# Group5Approved.net
KiCad netlist of a schematic drawn in EAGLE
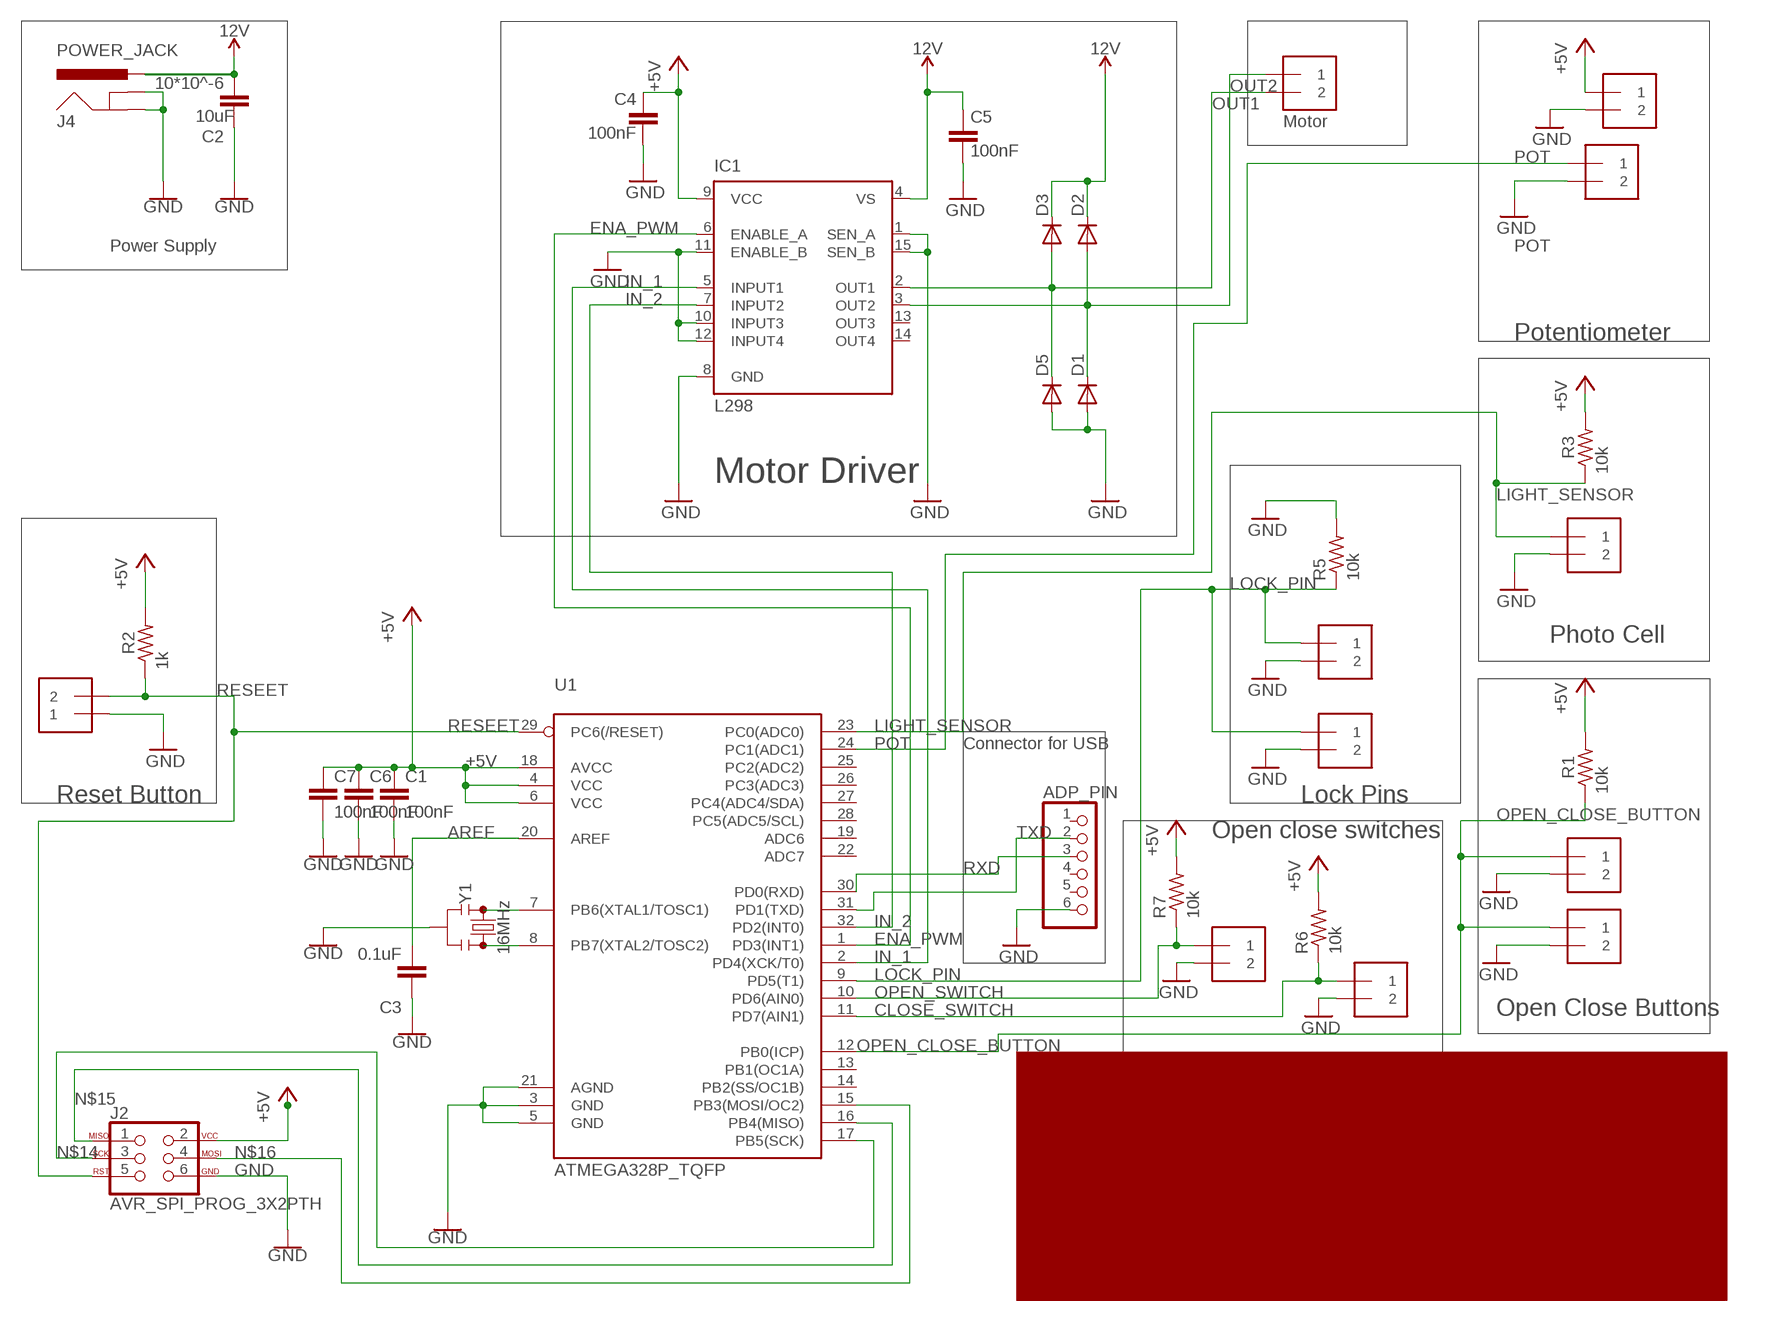
[diagram p0: schematic, sheet 1]

(export (version "E")
  (design (tool "Eeschema 10.0.6"))
  (components
    (comp (ref "ADP_PIN")
      (value "PINHD-1X6")
      (footprint "eagle-import:1X06")
      (libsource (lib "eagle-import") (part "PINHD-1X6"))
    )
    (comp (ref "C1")
      (value "100nF")
      (footprint "eagle-import:C0805")
      (libsource (lib "eagle-import") (part "C-EUC0805"))
    )
    (comp (ref "C2")
      (value "10*10^-6")
      (footprint "eagle-import:C0805")
      (fields (field (name "SPICEPREFIX") "C") (field (name "SPICEPREFIX_1") "10uF"))
      (libsource (lib "eagle-import") (part "C-EUC0805"))
    )
    (comp (ref "C3")
      (value "0.1uF")
      (footprint "eagle-import:C0805")
      (libsource (lib "eagle-import") (part "C-EUC0805"))
    )
    (comp (ref "C4")
      (value "100nF")
      (footprint "eagle-import:C0805")
      (libsource (lib "eagle-import") (part "C-EUC0805"))
    )
    (comp (ref "C5")
      (value "100nF")
      (footprint "eagle-import:C0805")
      (libsource (lib "eagle-import") (part "C-EUC0805"))
    )
    (comp (ref "C6")
      (value "100nF")
      (footprint "eagle-import:C0805")
      (libsource (lib "eagle-import") (part "C-EUC0805"))
    )
    (comp (ref "C7")
      (value "100nF")
      (footprint "eagle-import:C0805")
      (libsource (lib "eagle-import") (part "C-EUC0805"))
    )
    (comp (ref "CLOSESWITCH")
      (value "1X2-3.5MM")
      (footprint "eagle-import:1X2-3.5MM")
      (libsource (lib "eagle-import") (part "1X2-3.5MM"))
    )
    (comp (ref "D1")
      (value "DIODE-DO214AA")
      (footprint "eagle-import:DO214AA")
      (libsource (lib "eagle-import") (part "DIODE-DO214AA"))
    )
    (comp (ref "D2")
      (value "DIODE-DO214AA")
      (footprint "eagle-import:DO214AA")
      (libsource (lib "eagle-import") (part "DIODE-DO214AA"))
    )
    (comp (ref "D3")
      (value "DIODE-DO214AA")
      (footprint "eagle-import:DO214AA")
      (libsource (lib "eagle-import") (part "DIODE-DO214AA"))
    )
    (comp (ref "D5")
      (value "DIODE-DO214AA")
      (footprint "eagle-import:DO214AA")
      (libsource (lib "eagle-import") (part "DIODE-DO214AA"))
    )
    (comp (ref "IC1")
      (value "L298")
      (footprint "eagle-import:MULTIWATT-15")
      (fields (field (name "MPN") "L298N"))
      (libsource (lib "eagle-import") (part "L298"))
    )
    (comp (ref "INSIDE_BUTTON")
      (value "1X2-3.5MM")
      (footprint "eagle-import:1X2-3.5MM")
      (libsource (lib "eagle-import") (part "1X2-3.5MM"))
    )
    (comp (ref "J2")
      (value "AVR_SPI_PROG_3X2PTH")
      (footprint "eagle-import:2X3")
      (libsource (lib "eagle-import") (part "AVR_SPI_PROG_3X2PTH"))
    )
    (comp (ref "J4")
      (value "POWER_JACK")
      (footprint "eagle-import:POWER_JACK_PTH")
      (libsource (lib "eagle-import") (part "POWER_JACK"))
    )
    (comp (ref "LIGHT_SENSOR")
      (value "1X2-3.5MM")
      (footprint "eagle-import:1X2-3.5MM")
      (libsource (lib "eagle-import") (part "1X2-3.5MM"))
    )
    (comp (ref "LOCK_PIN1")
      (value "1X2-3.5MM")
      (footprint "eagle-import:1X2-3.5MM")
      (libsource (lib "eagle-import") (part "1X2-3.5MM"))
    )
    (comp (ref "LOCK_PIN2")
      (value "1X2-3.5MM")
      (footprint "eagle-import:1X2-3.5MM")
      (libsource (lib "eagle-import") (part "1X2-3.5MM"))
    )
    (comp (ref "MOTOR")
      (value "1X2-3.5MM")
      (footprint "eagle-import:1X2-3.5MM")
      (libsource (lib "eagle-import") (part "1X2-3.5MM"))
    )
    (comp (ref "OPEN_SWITCH")
      (value "1X2-3.5MM")
      (footprint "eagle-import:1X2-3.5MM")
      (libsource (lib "eagle-import") (part "1X2-3.5MM"))
    )
    (comp (ref "OUTSIDE_BUTTON")
      (value "1X2-3.5MM")
      (footprint "eagle-import:1X2-3.5MM")
      (libsource (lib "eagle-import") (part "1X2-3.5MM"))
    )
    (comp (ref "POT")
      (value "1X2-3.5MM")
      (footprint "eagle-import:1X2-3.5MM")
      (libsource (lib "eagle-import") (part "1X2-3.5MM"))
    )
    (comp (ref "POTPOWER")
      (value "1X2-3.5MM")
      (footprint "eagle-import:1X2-3.5MM")
      (libsource (lib "eagle-import") (part "1X2-3.5MM"))
    )
    (comp (ref "R1")
      (value "10k")
      (footprint "eagle-import:M0805")
      (libsource (lib "eagle-import") (part "R-US_M0805"))
    )
    (comp (ref "R2")
      (value "1k")
      (footprint "eagle-import:M0805")
      (libsource (lib "eagle-import") (part "R-US_M0805"))
    )
    (comp (ref "R3")
      (value "10k")
      (footprint "eagle-import:M0805")
      (libsource (lib "eagle-import") (part "R-US_M0805"))
    )
    (comp (ref "R5")
      (value "10k")
      (footprint "eagle-import:M0805")
      (libsource (lib "eagle-import") (part "R-US_M0805"))
    )
    (comp (ref "R6")
      (value "10k")
      (footprint "eagle-import:M0805")
      (libsource (lib "eagle-import") (part "R-US_M0805"))
    )
    (comp (ref "R7")
      (value "10k")
      (footprint "eagle-import:M0805")
      (libsource (lib "eagle-import") (part "R-US_M0805"))
    )
    (comp (ref "RESETBUTTON")
      (value "1X2-3.5MM")
      (footprint "eagle-import:1X2-3.5MM")
      (libsource (lib "eagle-import") (part "1X2-3.5MM"))
    )
    (comp (ref "U1")
      (value "ATMEGA328P_TQFP")
      (footprint "eagle-import:TQFP32-08")
      (libsource (lib "eagle-import") (part "ATMEGA328P_TQFP"))
    )
    (comp (ref "Y1")
      (value "16MHz")
      (footprint "eagle-import:RESONATOR-SMD-3.2X1.3")
      (libsource (lib "eagle-import") (part "RESONATOR-16MHZSMD_3.2X1.3"))
    )
  )
  (nets
    (net (code "1") (name "+5V") (class "Default")
      (node (ref "C1") (pin "1") (pinfunction "1_1") (pintype "passive"))
      (node (ref "C4") (pin "1") (pinfunction "1_1") (pintype "passive"))
      (node (ref "C6") (pin "1") (pinfunction "1_1") (pintype "passive"))
      (node (ref "C7") (pin "1") (pinfunction "1_1") (pintype "passive"))
      (node (ref "IC1") (pin "9") (pinfunction "VCC_9") (pintype "power_in"))
      (node (ref "J2") (pin "2") (pinfunction "2_2") (pintype "passive"))
      (node (ref "POTPOWER") (pin "1") (pinfunction "1_1") (pintype "passive"))
      (node (ref "R1") (pin "2") (pinfunction "2_2") (pintype "passive"))
      (node (ref "R2") (pin "2") (pinfunction "2_2") (pintype "passive"))
      (node (ref "R3") (pin "2") (pinfunction "2_2") (pintype "passive"))
      (node (ref "R6") (pin "2") (pinfunction "2_2") (pintype "passive"))
      (node (ref "R7") (pin "2") (pinfunction "2_2") (pintype "passive"))
      (node (ref "U1") (pin "18") (pinfunction "AVCC_18") (pintype "bidirectional"))
      (node (ref "U1") (pin "4") (pinfunction "VCC_4") (pintype "bidirectional"))
      (node (ref "U1") (pin "6") (pinfunction "VCC_6") (pintype "bidirectional"))
    )
    (net (code "2") (name "/AREF") (class "Default")
      (node (ref "C3") (pin "2") (pinfunction "2_2") (pintype "passive"))
      (node (ref "U1") (pin "20") (pinfunction "AREF_20") (pintype "bidirectional"))
    )
    (net (code "3") (name "/CLOSE_SWITCH") (class "Default")
      (node (ref "CLOSESWITCH") (pin "1") (pinfunction "1_1") (pintype "passive"))
      (node (ref "R6") (pin "1") (pinfunction "1_1") (pintype "passive"))
      (node (ref "U1") (pin "11") (pinfunction "PD7(AIN1)_11") (pintype "bidirectional"))
    )
    (net (code "4") (name "/ENA_PWM") (class "Default")
      (node (ref "IC1") (pin "6") (pinfunction "ENABLE_A_6") (pintype "input"))
      (node (ref "U1") (pin "1") (pinfunction "PD3(INT1)_1") (pintype "bidirectional"))
    )
    (net (code "5") (name "/IN_1") (class "Default")
      (node (ref "IC1") (pin "5") (pinfunction "INPUT1_5") (pintype "input"))
      (node (ref "U1") (pin "2") (pinfunction "PD4(XCK/T0)_2") (pintype "bidirectional"))
    )
    (net (code "6") (name "/IN_2") (class "Default")
      (node (ref "IC1") (pin "7") (pinfunction "INPUT2_7") (pintype "input"))
      (node (ref "U1") (pin "32") (pinfunction "PD2(INT0)_32") (pintype "bidirectional"))
    )
    (net (code "7") (name "/LIGHT_SENSOR") (class "Default")
      (node (ref "LIGHT_SENSOR") (pin "1") (pinfunction "1_1") (pintype "passive"))
      (node (ref "R3") (pin "1") (pinfunction "1_1") (pintype "passive"))
      (node (ref "U1") (pin "23") (pinfunction "PC0(ADC0)_23") (pintype "bidirectional"))
    )
    (net (code "8") (name "/LOCK_PIN") (class "Default")
      (node (ref "LOCK_PIN1") (pin "1") (pinfunction "1_1") (pintype "passive"))
      (node (ref "LOCK_PIN2") (pin "1") (pinfunction "1_1") (pintype "passive"))
      (node (ref "R5") (pin "1") (pinfunction "1_1") (pintype "passive"))
      (node (ref "U1") (pin "9") (pinfunction "PD5(T1)_9") (pintype "bidirectional"))
    )
    (net (code "9") (name "/N$14") (class "Default")
      (node (ref "J2") (pin "3") (pinfunction "3_3") (pintype "passive"))
      (node (ref "U1") (pin "17") (pinfunction "PB5(SCK)_17") (pintype "bidirectional"))
    )
    (net (code "10") (name "/N$15") (class "Default")
      (node (ref "J2") (pin "1") (pinfunction "1_1") (pintype "passive"))
      (node (ref "U1") (pin "16") (pinfunction "PB4(MISO)_16") (pintype "bidirectional"))
    )
    (net (code "11") (name "/N$16") (class "Default")
      (node (ref "J2") (pin "4") (pinfunction "4_4") (pintype "passive"))
      (node (ref "U1") (pin "15") (pinfunction "PB3(MOSI/OC2)_15") (pintype "bidirectional"))
    )
    (net (code "12") (name "/OPEN_CLOSE_BUTTON") (class "Default")
      (node (ref "INSIDE_BUTTON") (pin "1") (pinfunction "1_1") (pintype "passive"))
      (node (ref "OUTSIDE_BUTTON") (pin "1") (pinfunction "1_1") (pintype "passive"))
      (node (ref "R1") (pin "1") (pinfunction "1_1") (pintype "passive"))
      (node (ref "U1") (pin "12") (pinfunction "PB0(ICP)_12") (pintype "bidirectional"))
    )
    (net (code "13") (name "/OPEN_SWITCH") (class "Default")
      (node (ref "OPEN_SWITCH") (pin "1") (pinfunction "1_1") (pintype "passive"))
      (node (ref "R7") (pin "1") (pinfunction "1_1") (pintype "passive"))
      (node (ref "U1") (pin "10") (pinfunction "PD6(AIN0)_10") (pintype "bidirectional"))
    )
    (net (code "14") (name "/OUT1") (class "Default")
      (node (ref "D3") (pin "A") (pinfunction "A_A") (pintype "passive"))
      (node (ref "D5") (pin "C") (pinfunction "C_C") (pintype "passive"))
      (node (ref "IC1") (pin "2") (pinfunction "OUT1_2") (pintype "output"))
      (node (ref "MOTOR") (pin "2") (pinfunction "2_2") (pintype "passive"))
    )
    (net (code "15") (name "/OUT2") (class "Default")
      (node (ref "D1") (pin "C") (pinfunction "C_C") (pintype "passive"))
      (node (ref "D2") (pin "A") (pinfunction "A_A") (pintype "passive"))
      (node (ref "IC1") (pin "3") (pinfunction "OUT2_3") (pintype "output"))
      (node (ref "MOTOR") (pin "1") (pinfunction "1_1") (pintype "passive"))
    )
    (net (code "16") (name "/POT") (class "Default")
      (node (ref "POT") (pin "1") (pinfunction "1_1") (pintype "passive"))
      (node (ref "U1") (pin "24") (pinfunction "PC1(ADC1)_24") (pintype "bidirectional"))
    )
    (net (code "17") (name "/RESEET") (class "Default")
      (node (ref "J2") (pin "5") (pinfunction "5_5") (pintype "passive"))
      (node (ref "R2") (pin "1") (pinfunction "1_1") (pintype "passive"))
      (node (ref "RESETBUTTON") (pin "2") (pinfunction "2_2") (pintype "passive"))
      (node (ref "U1") (pin "29") (pinfunction "PC6(/RESET)_29") (pintype "bidirectional"))
    )
    (net (code "18") (name "/RXD") (class "Default")
      (node (ref "ADP_PIN") (pin "3") (pinfunction "3_3") (pintype "passive"))
      (node (ref "U1") (pin "30") (pinfunction "PD0(RXD)_30") (pintype "bidirectional"))
    )
    (net (code "19") (name "/TXD") (class "Default")
      (node (ref "ADP_PIN") (pin "2") (pinfunction "2_2") (pintype "passive"))
      (node (ref "U1") (pin "31") (pinfunction "PD1(TXD)_31") (pintype "bidirectional"))
    )
    (net (code "20") (name "12V") (class "Default")
      (node (ref "C2") (pin "2") (pinfunction "2_2") (pintype "passive"))
      (node (ref "C5") (pin "1") (pinfunction "1_1") (pintype "passive"))
      (node (ref "D2") (pin "C") (pinfunction "C_C") (pintype "passive"))
      (node (ref "D3") (pin "C") (pinfunction "C_C") (pintype "passive"))
      (node (ref "IC1") (pin "4") (pinfunction "VS_4") (pintype "power_in"))
      (node (ref "J4") (pin "PWR") (pinfunction "PWR_PWR") (pintype "bidirectional"))
    )
    (net (code "21") (name "GND") (class "Default")
      (node (ref "ADP_PIN") (pin "6") (pinfunction "6_6") (pintype "passive"))
      (node (ref "C1") (pin "2") (pinfunction "2_2") (pintype "passive"))
      (node (ref "C2") (pin "1") (pinfunction "1_1") (pintype "passive"))
      (node (ref "C3") (pin "1") (pinfunction "1_1") (pintype "passive"))
      (node (ref "C4") (pin "2") (pinfunction "2_2") (pintype "passive"))
      (node (ref "C5") (pin "2") (pinfunction "2_2") (pintype "passive"))
      (node (ref "C6") (pin "2") (pinfunction "2_2") (pintype "passive"))
      (node (ref "C7") (pin "2") (pinfunction "2_2") (pintype "passive"))
      (node (ref "CLOSESWITCH") (pin "2") (pinfunction "2_2") (pintype "passive"))
      (node (ref "D1") (pin "A") (pinfunction "A_A") (pintype "passive"))
      (node (ref "D5") (pin "A") (pinfunction "A_A") (pintype "passive"))
      (node (ref "IC1") (pin "1") (pinfunction "SEN_A_1") (pintype "input"))
      (node (ref "IC1") (pin "10") (pinfunction "INPUT3_10") (pintype "input"))
      (node (ref "IC1") (pin "11") (pinfunction "ENABLE_B_11") (pintype "input"))
      (node (ref "IC1") (pin "12") (pinfunction "INPUT4_12") (pintype "input"))
      (node (ref "IC1") (pin "15") (pinfunction "SEN_B_15") (pintype "input"))
      (node (ref "IC1") (pin "8") (pinfunction "GND_8") (pintype "power_in"))
      (node (ref "INSIDE_BUTTON") (pin "2") (pinfunction "2_2") (pintype "passive"))
      (node (ref "J2") (pin "6") (pinfunction "6_6") (pintype "passive"))
      (node (ref "J4") (pin "GND") (pinfunction "GND_GND") (pintype "bidirectional"))
      (node (ref "J4") (pin "GNDBREAK") (pinfunction "GNDBREAK_GNDBREAK") (pintype "bidirectional"))
      (node (ref "LIGHT_SENSOR") (pin "2") (pinfunction "2_2") (pintype "passive"))
      (node (ref "LOCK_PIN1") (pin "2") (pinfunction "2_2") (pintype "passive"))
      (node (ref "LOCK_PIN2") (pin "2") (pinfunction "2_2") (pintype "passive"))
      (node (ref "OPEN_SWITCH") (pin "2") (pinfunction "2_2") (pintype "passive"))
      (node (ref "OUTSIDE_BUTTON") (pin "2") (pinfunction "2_2") (pintype "passive"))
      (node (ref "POT") (pin "2") (pinfunction "2_2") (pintype "passive"))
      (node (ref "POTPOWER") (pin "2") (pinfunction "2_2") (pintype "passive"))
      (node (ref "R5") (pin "2") (pinfunction "2_2") (pintype "passive"))
      (node (ref "RESETBUTTON") (pin "1") (pinfunction "1_1") (pintype "passive"))
      (node (ref "U1") (pin "21") (pinfunction "AGND_21") (pintype "bidirectional"))
      (node (ref "U1") (pin "3") (pinfunction "GND_3") (pintype "bidirectional"))
      (node (ref "U1") (pin "5") (pinfunction "GND_5") (pintype "bidirectional"))
      (node (ref "Y1") (pin "2") (pinfunction "2_2") (pintype "passive"))
    )
    (net (code "22") (name "Net-(U1-PB6(XTAL1{slash}TOSC1))") (class "Default")
      (node (ref "U1") (pin "7") (pinfunction "PB6(XTAL1/TOSC1)_7") (pintype "bidirectional"))
      (node (ref "Y1") (pin "1") (pinfunction "1_1") (pintype "passive"))
    )
    (net (code "23") (name "Net-(U1-PB7(XTAL2{slash}TOSC2))") (class "Default")
      (node (ref "U1") (pin "8") (pinfunction "PB7(XTAL2/TOSC2)_8") (pintype "bidirectional"))
      (node (ref "Y1") (pin "3") (pinfunction "3_3") (pintype "passive"))
    )
    (net (code "24") (name "unconnected-(ADP_PIN-Pad1)") (class "Default")
      (node (ref "ADP_PIN") (pin "1") (pinfunction "1_1") (pintype "passive"))
    )
    (net (code "25") (name "unconnected-(ADP_PIN-Pad4)") (class "Default")
      (node (ref "ADP_PIN") (pin "4") (pinfunction "4_4") (pintype "passive"))
    )
    (net (code "26") (name "unconnected-(ADP_PIN-Pad5)") (class "Default")
      (node (ref "ADP_PIN") (pin "5") (pinfunction "5_5") (pintype "passive"))
    )
    (net (code "27") (name "unconnected-(IC1-OUT3-Pad13)") (class "Default")
      (node (ref "IC1") (pin "13") (pinfunction "OUT3_13") (pintype "output"))
    )
    (net (code "28") (name "unconnected-(IC1-OUT4-Pad14)") (class "Default")
      (node (ref "IC1") (pin "14") (pinfunction "OUT4_14") (pintype "output"))
    )
    (net (code "29") (name "unconnected-(U1-ADC6-Pad19)") (class "Default")
      (node (ref "U1") (pin "19") (pinfunction "ADC6_19") (pintype "bidirectional"))
    )
    (net (code "30") (name "unconnected-(U1-ADC7-Pad22)") (class "Default")
      (node (ref "U1") (pin "22") (pinfunction "ADC7_22") (pintype "bidirectional"))
    )
    (net (code "31") (name "unconnected-(U1-PB1(OC1A)-Pad13)") (class "Default")
      (node (ref "U1") (pin "13") (pinfunction "PB1(OC1A)_13") (pintype "bidirectional"))
    )
    (net (code "32") (name "unconnected-(U1-PB2(SS{slash}OC1B)-Pad14)") (class "Default")
      (node (ref "U1") (pin "14") (pinfunction "PB2(SS/OC1B)_14") (pintype "bidirectional"))
    )
    (net (code "33") (name "unconnected-(U1-PC2(ADC2)-Pad25)") (class "Default")
      (node (ref "U1") (pin "25") (pinfunction "PC2(ADC2)_25") (pintype "bidirectional"))
    )
    (net (code "34") (name "unconnected-(U1-PC3(ADC3)-Pad26)") (class "Default")
      (node (ref "U1") (pin "26") (pinfunction "PC3(ADC3)_26") (pintype "bidirectional"))
    )
    (net (code "35") (name "unconnected-(U1-PC4(ADC4{slash}SDA)-Pad27)") (class "Default")
      (node (ref "U1") (pin "27") (pinfunction "PC4(ADC4/SDA)_27") (pintype "bidirectional"))
    )
    (net (code "36") (name "unconnected-(U1-PC5(ADC5{slash}SCL)-Pad28)") (class "Default")
      (node (ref "U1") (pin "28") (pinfunction "PC5(ADC5/SCL)_28") (pintype "bidirectional"))
    )
  )
)
